# DiPHO_MCU.net
KiCad netlist of a schematic drawn in Altium Designer
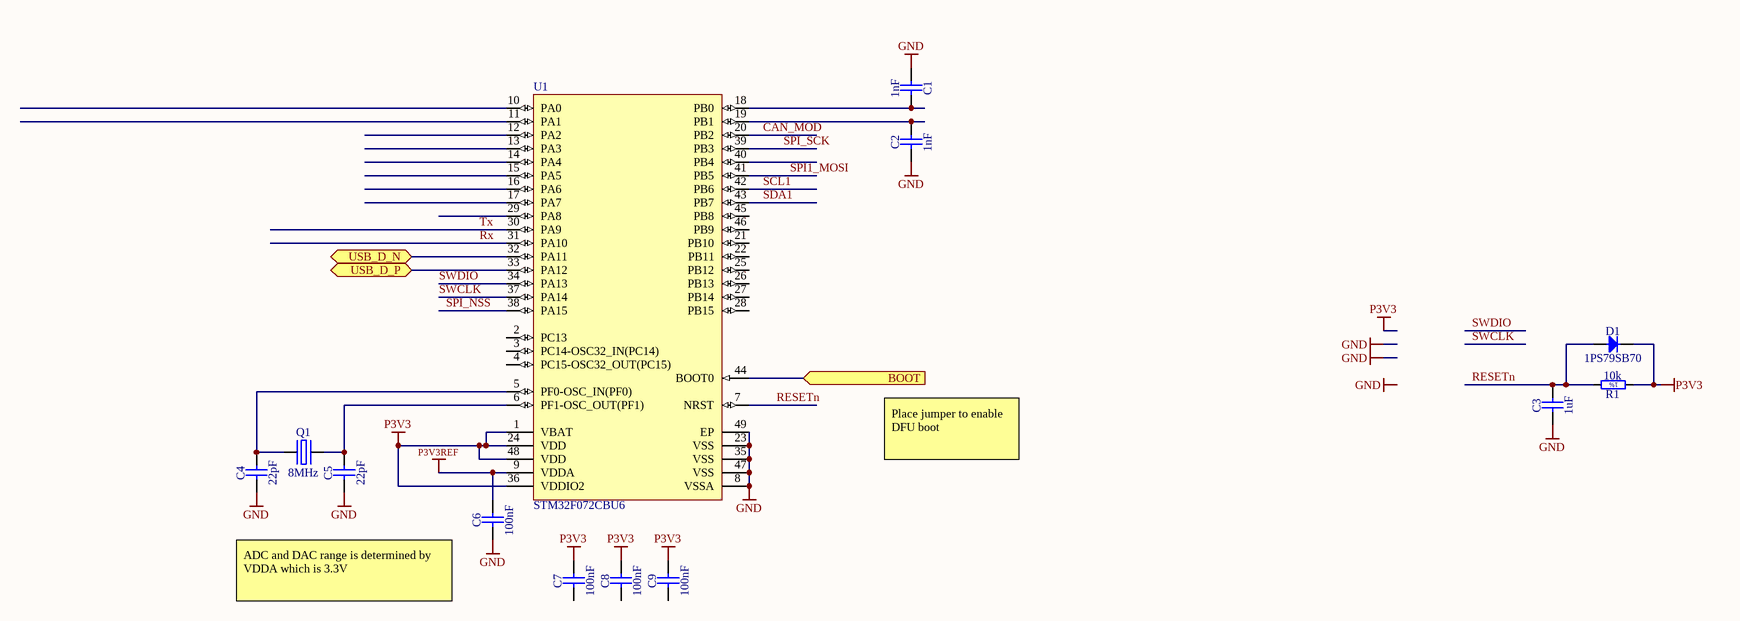
[diagram p0: DiPHO_MCU.SchDoc]

(export (version "E")
  (design (tool "Eeschema 10.0.6"))
  (components
    (comp (ref "C1")
      (value "1nF")
      (footprint "CAPC1005X55N")
      (description "Non-polarised capacitor")
      (fields
        (field (name "PART NUMBER") "CC0402_1NF_50V_5%_C0G")
        (field (name "VOLTAGE") "50V")
        (field (name "AUTHOR") "CERN DEM BC")
      )
      (libsource (lib "Capacitors") (part "Capacitor - non polarized"))
    )
    (comp (ref "C2")
      (value "1nF")
      (footprint "CAPC1005X55N")
      (description "Non-polarised capacitor")
      (fields
        (field (name "PART NUMBER") "CC0402_1NF_50V_5%_C0G")
        (field (name "VOLTAGE") "50V")
        (field (name "AUTHOR") "CERN DEM BC")
      )
      (libsource (lib "Capacitors") (part "Capacitor - non polarized"))
    )
    (comp (ref "C3")
      (value "1uF")
      (footprint "CAPC1608X87N")
      (description "Non-polarised capacitor")
      (fields
        (field (name "PART NUMBER") "CC0603_1UF_16V_10%_X7R")
        (field (name "VOLTAGE") "16V")
        (field (name "AUTHOR") "CERN DEM JLC")
      )
      (libsource (lib "Capacitors") (part "Capacitor - non polarized"))
    )
    (comp (ref "C4")
      (value "22pF")
      (footprint "CAPC1005X55N")
      (description "Non-polarised capacitor")
      (fields
        (field (name "PART NUMBER") "CC0402_22PF_50V_5%_C0G")
        (field (name "VOLTAGE") "50V")
        (field (name "AUTHOR") "CERN DEM JLC")
      )
      (libsource (lib "Capacitors") (part "Capacitor - non polarized"))
    )
    (comp (ref "C5")
      (value "22pF")
      (footprint "CAPC1005X55N")
      (description "Non-polarised capacitor")
      (fields
        (field (name "PART NUMBER") "CC0402_22PF_50V_5%_C0G")
        (field (name "VOLTAGE") "50V")
        (field (name "AUTHOR") "CERN DEM JLC")
      )
      (libsource (lib "Capacitors") (part "Capacitor - non polarized"))
    )
    (comp (ref "C6")
      (value "100nF")
      (footprint "CAPC1005X55N")
      (description "Non-polarised capacitor")
      (fields
        (field (name "PART NUMBER") "CC0402_100NF_16V_10%_X7R")
        (field (name "VOLTAGE") "16V")
        (field (name "AUTHOR") "CERN DEM JLC")
      )
      (libsource (lib "Capacitors") (part "Capacitor - non polarized"))
    )
    (comp (ref "C7")
      (value "100nF")
      (footprint "CAPC1005X55N")
      (description "Non-polarised capacitor")
      (fields
        (field (name "PART NUMBER") "CC0402_100NF_16V_10%_X7R")
        (field (name "VOLTAGE") "16V")
        (field (name "AUTHOR") "CERN DEM JLC")
      )
      (libsource (lib "Capacitors") (part "Capacitor - non polarized"))
    )
    (comp (ref "C8")
      (value "100nF")
      (footprint "CAPC1005X55N")
      (description "Non-polarised capacitor")
      (fields
        (field (name "PART NUMBER") "CC0402_100NF_16V_10%_X7R")
        (field (name "VOLTAGE") "16V")
        (field (name "AUTHOR") "CERN DEM JLC")
      )
      (libsource (lib "Capacitors") (part "Capacitor - non polarized"))
    )
    (comp (ref "C9")
      (value "100nF")
      (footprint "CAPC1005X55N")
      (description "Non-polarised capacitor")
      (fields
        (field (name "PART NUMBER") "CC0402_100NF_16V_10%_X7R")
        (field (name "VOLTAGE") "16V")
        (field (name "AUTHOR") "CERN DEM JLC")
      )
      (libsource (lib "Capacitors") (part "Capacitor - non polarized"))
    )
    (comp (ref "D1")
      (value "1PS79SB70")
      (footprint "SODFL1608X65N")
      (description "Diode")
      (fields (field (name "VOLTAGE") "70V") (field (name "POWER") "70mA") (field (name "AUTHOR") "GK"))
      (libsource (lib "Diodes") (part "D_1PS79SB70"))
    )
    (comp (ref "Q1")
      (value "8MHz")
      (footprint "XTAL_TXC_7A")
      (description "Quartz Crystal")
      (fields
        (field (name "PART NUMBER") "XTAL_8MHZ_TXC_7A-8.000MAAE-T")
        (field (name "MANUFACTURER") "TXC CORPORATION")
        (field (name "AUTHOR") "CERN DEM JLC")
      )
      (libsource (lib "ICs And Semiconductors") (part "Quartz Crystal"))
    )
    (comp (ref "R1")
      (value "10k")
      (footprint "RESC1005X40N")
      (description "Resistor - 1%")
      (fields
        (field (name "PART NUMBER") "R0402_10K_1%_0.0625W_100PPM")
        (field (name "POWER") "0.0625W")
        (field (name "AUTHOR") "CERN DEM JLC")
      )
      (libsource (lib "Resistors") (part "Resistor - 1%"))
    )
    (comp (ref "U1")
      (value "STM32F072CBU6")
      (footprint "STM-UFQFPN48_L")
      (fields (field (name "MANUFACTURER") "STMicroelectronics"))
      (libsource (lib "Altium Content Vault") (part "MC-ARM-STM32F072-UFQFPN48"))
    )
  )
  (nets
    (net (code "1") (name "/BOOT") (class "Default")
      (node (ref "U1") (pin "44") (pinfunction "BOOT0_44") (pintype "input"))
    )
    (net (code "2") (name "/CAN_MOD") (class "Default")
      (node (ref "U1") (pin "20") (pinfunction "PB2_20") (pintype "bidirectional"))
    )
    (net (code "3") (name "/RESETn") (class "Default")
      (node (ref "C3") (pin "2") (pinfunction "2_2") (pintype "passive"))
      (node (ref "D1") (pin "2") (pinfunction "A_2") (pintype "passive"))
      (node (ref "R1") (pin "2") (pinfunction "2_2") (pintype "passive"))
      (node (ref "U1") (pin "7") (pinfunction "NRST_7") (pintype "bidirectional"))
    )
    (net (code "4") (name "/Rx") (class "Default")
      (node (ref "U1") (pin "31") (pinfunction "PA10_31") (pintype "bidirectional"))
    )
    (net (code "5") (name "/SCL1") (class "Default")
      (node (ref "U1") (pin "42") (pinfunction "PB6_42") (pintype "bidirectional"))
    )
    (net (code "6") (name "/SDA1") (class "Default")
      (node (ref "U1") (pin "43") (pinfunction "PB7_43") (pintype "bidirectional"))
    )
    (net (code "7") (name "/SPI1_MOSI") (class "Default")
      (node (ref "U1") (pin "41") (pinfunction "PB5_41") (pintype "bidirectional"))
    )
    (net (code "8") (name "/SPI_NSS") (class "Default")
      (node (ref "U1") (pin "38") (pinfunction "PA15_38") (pintype "bidirectional"))
    )
    (net (code "9") (name "/SPI_SCK") (class "Default")
      (node (ref "U1") (pin "39") (pinfunction "PB3_39") (pintype "bidirectional"))
    )
    (net (code "10") (name "/SWCLK") (class "Default")
      (node (ref "U1") (pin "37") (pinfunction "PA14_37") (pintype "bidirectional"))
    )
    (net (code "11") (name "/SWDIO") (class "Default")
      (node (ref "U1") (pin "34") (pinfunction "PA13_34") (pintype "bidirectional"))
    )
    (net (code "12") (name "/Tx") (class "Default")
      (node (ref "U1") (pin "30") (pinfunction "PA9_30") (pintype "bidirectional"))
    )
    (net (code "13") (name "/USB_D_N") (class "Default")
      (node (ref "U1") (pin "32") (pinfunction "PA11_32") (pintype "bidirectional"))
    )
    (net (code "14") (name "/USB_D_P") (class "Default")
      (node (ref "U1") (pin "33") (pinfunction "PA12_33") (pintype "bidirectional"))
    )
    (net (code "15") (name "GND") (class "Default")
      (node (ref "C1") (pin "1") (pinfunction "1_1") (pintype "passive"))
      (node (ref "C2") (pin "1") (pinfunction "1_1") (pintype "passive"))
      (node (ref "C3") (pin "1") (pinfunction "1_1") (pintype "passive"))
      (node (ref "C4") (pin "1") (pinfunction "1_1") (pintype "passive"))
      (node (ref "C5") (pin "1") (pinfunction "1_1") (pintype "passive"))
      (node (ref "C6") (pin "1") (pinfunction "1_1") (pintype "passive"))
      (node (ref "U1") (pin "23") (pinfunction "VSS_23") (pintype "power_in"))
      (node (ref "U1") (pin "35") (pinfunction "VSS_35") (pintype "power_in"))
      (node (ref "U1") (pin "47") (pinfunction "VSS_47") (pintype "power_in"))
      (node (ref "U1") (pin "49") (pinfunction "EP_49") (pintype "power_in"))
      (node (ref "U1") (pin "8") (pinfunction "VSSA_8") (pintype "power_in"))
    )
    (net (code "16") (name "Net-(Q1-OSC1)") (class "Default")
      (node (ref "C4") (pin "2") (pinfunction "2_2") (pintype "passive"))
      (node (ref "Q1") (pin "1") (pinfunction "OSC1_1") (pintype "passive"))
      (node (ref "U1") (pin "5") (pinfunction "PF0-OSC_IN(PF0)_5") (pintype "bidirectional"))
    )
    (net (code "17") (name "Net-(Q1-OSC2)") (class "Default")
      (node (ref "C5") (pin "2") (pinfunction "2_2") (pintype "passive"))
      (node (ref "Q1") (pin "2") (pinfunction "OSC2_2") (pintype "passive"))
      (node (ref "U1") (pin "6") (pinfunction "PF1-OSC_OUT(PF1)_6") (pintype "bidirectional"))
    )
    (net (code "18") (name "Net-(U1-PB0)") (class "Default")
      (node (ref "C1") (pin "2") (pinfunction "2_2") (pintype "passive"))
      (node (ref "U1") (pin "18") (pinfunction "PB0_18") (pintype "bidirectional"))
    )
    (net (code "19") (name "Net-(U1-PB1)") (class "Default")
      (node (ref "C2") (pin "2") (pinfunction "2_2") (pintype "passive"))
      (node (ref "U1") (pin "19") (pinfunction "PB1_19") (pintype "bidirectional"))
    )
    (net (code "20") (name "P3V3") (class "Default")
      (node (ref "C7") (pin "2") (pinfunction "2_2") (pintype "passive"))
      (node (ref "C8") (pin "2") (pinfunction "2_2") (pintype "passive"))
      (node (ref "C9") (pin "2") (pinfunction "2_2") (pintype "passive"))
      (node (ref "D1") (pin "1") (pinfunction "C_1") (pintype "passive"))
      (node (ref "R1") (pin "1") (pinfunction "1_1") (pintype "passive"))
      (node (ref "U1") (pin "1") (pinfunction "VBAT_1") (pintype "power_in"))
      (node (ref "U1") (pin "24") (pinfunction "VDD_24") (pintype "power_in"))
      (node (ref "U1") (pin "36") (pinfunction "VDDIO2_36") (pintype "power_in"))
      (node (ref "U1") (pin "48") (pinfunction "VDD_48") (pintype "power_in"))
    )
    (net (code "21") (name "P3V3REF") (class "Default")
      (node (ref "C6") (pin "2") (pinfunction "2_2") (pintype "passive"))
      (node (ref "U1") (pin "9") (pinfunction "VDDA_9") (pintype "power_in"))
    )
    (net (code "22") (name "unconnected-(C7-Pad1)") (class "Default")
      (node (ref "C7") (pin "1") (pinfunction "1_1") (pintype "passive"))
    )
    (net (code "23") (name "unconnected-(C8-Pad1)") (class "Default")
      (node (ref "C8") (pin "1") (pinfunction "1_1") (pintype "passive"))
    )
    (net (code "24") (name "unconnected-(C9-Pad1)") (class "Default")
      (node (ref "C9") (pin "1") (pinfunction "1_1") (pintype "passive"))
    )
    (net (code "25") (name "unconnected-(U1-PA0-Pad10)") (class "Default")
      (node (ref "U1") (pin "10") (pinfunction "PA0_10") (pintype "bidirectional"))
    )
    (net (code "26") (name "unconnected-(U1-PA1-Pad11)") (class "Default")
      (node (ref "U1") (pin "11") (pinfunction "PA1_11") (pintype "bidirectional"))
    )
    (net (code "27") (name "unconnected-(U1-PA2-Pad12)") (class "Default")
      (node (ref "U1") (pin "12") (pinfunction "PA2_12") (pintype "bidirectional"))
    )
    (net (code "28") (name "unconnected-(U1-PA3-Pad13)") (class "Default")
      (node (ref "U1") (pin "13") (pinfunction "PA3_13") (pintype "bidirectional"))
    )
    (net (code "29") (name "unconnected-(U1-PA4-Pad14)") (class "Default")
      (node (ref "U1") (pin "14") (pinfunction "PA4_14") (pintype "bidirectional"))
    )
    (net (code "30") (name "unconnected-(U1-PA5-Pad15)") (class "Default")
      (node (ref "U1") (pin "15") (pinfunction "PA5_15") (pintype "bidirectional"))
    )
    (net (code "31") (name "unconnected-(U1-PA6-Pad16)") (class "Default")
      (node (ref "U1") (pin "16") (pinfunction "PA6_16") (pintype "bidirectional"))
    )
    (net (code "32") (name "unconnected-(U1-PA7-Pad17)") (class "Default")
      (node (ref "U1") (pin "17") (pinfunction "PA7_17") (pintype "bidirectional"))
    )
    (net (code "33") (name "unconnected-(U1-PA8-Pad29)") (class "Default")
      (node (ref "U1") (pin "29") (pinfunction "PA8_29") (pintype "bidirectional"))
    )
    (net (code "34") (name "unconnected-(U1-PB4-Pad40)") (class "Default")
      (node (ref "U1") (pin "40") (pinfunction "PB4_40") (pintype "bidirectional"))
    )
    (net (code "35") (name "unconnected-(U1-PB8-Pad45)") (class "Default")
      (node (ref "U1") (pin "45") (pinfunction "PB8_45") (pintype "bidirectional"))
    )
    (net (code "36") (name "unconnected-(U1-PB9-Pad46)") (class "Default")
      (node (ref "U1") (pin "46") (pinfunction "PB9_46") (pintype "bidirectional"))
    )
    (net (code "37") (name "unconnected-(U1-PB10-Pad21)") (class "Default")
      (node (ref "U1") (pin "21") (pinfunction "PB10_21") (pintype "bidirectional"))
    )
    (net (code "38") (name "unconnected-(U1-PB11-Pad22)") (class "Default")
      (node (ref "U1") (pin "22") (pinfunction "PB11_22") (pintype "bidirectional"))
    )
    (net (code "39") (name "unconnected-(U1-PB12-Pad25)") (class "Default")
      (node (ref "U1") (pin "25") (pinfunction "PB12_25") (pintype "bidirectional"))
    )
    (net (code "40") (name "unconnected-(U1-PB13-Pad26)") (class "Default")
      (node (ref "U1") (pin "26") (pinfunction "PB13_26") (pintype "bidirectional"))
    )
    (net (code "41") (name "unconnected-(U1-PB14-Pad27)") (class "Default")
      (node (ref "U1") (pin "27") (pinfunction "PB14_27") (pintype "bidirectional"))
    )
    (net (code "42") (name "unconnected-(U1-PB15-Pad28)") (class "Default")
      (node (ref "U1") (pin "28") (pinfunction "PB15_28") (pintype "bidirectional"))
    )
    (net (code "43") (name "unconnected-(U1-PC13-Pad2)") (class "Default")
      (node (ref "U1") (pin "2") (pinfunction "PC13_2") (pintype "bidirectional"))
    )
    (net (code "44") (name "unconnected-(U1-PC14-OSC32_IN(PC14)-Pad3)") (class "Default")
      (node (ref "U1") (pin "3") (pinfunction "PC14-OSC32_IN(PC14)_3") (pintype "bidirectional"))
    )
    (net (code "45") (name "unconnected-(U1-PC15-OSC32_OUT(PC15)-Pad4)") (class "Default")
      (node (ref "U1") (pin "4") (pinfunction "PC15-OSC32_OUT(PC15)_4") (pintype "bidirectional"))
    )
  )
)
